# design.net
KiCad netlist of a schematic drawn in EasyEDA
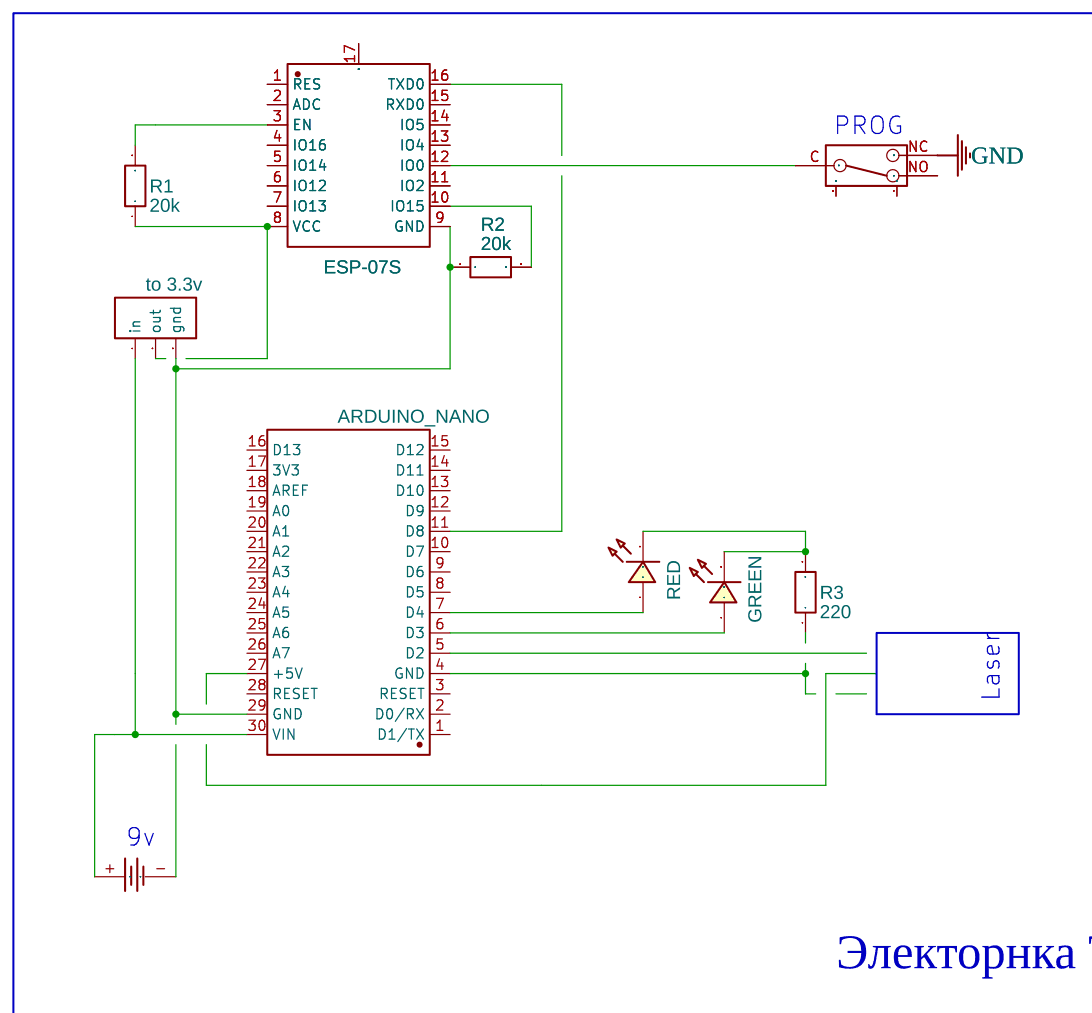
[diagram p0: schematic sheet]

(export (version "E")
  (design (tool "Eeschema 10.0.6"))
  (components
    (comp (ref "B1")
      (value "CR1220-2")
      (fields (field (name "BOM_Supplier Part") "C70381"))
      (libsource (lib "") (part "CR1220-2"))
    )
    (comp (ref "GREEN")
      (value "LED-0603_R")
      (fields
        (field (name "BOM_Manufacturer Part") "19-217/R6C-AL1M2VY/3T")
        (field (name "BOM_Supplier Part") "C72044")
      )
      (libsource (lib "") (part "LED-0603_R_1"))
    )
    (comp (ref "LED1")
      (value "RED")
      (fields
        (field (name "BOM_Manufacturer Part") "19-217/R6C-AL1M2VY/3T")
        (field (name "BOM_Supplier Part") "C72044")
      )
      (libsource (lib "") (part "LED-0603_R"))
    )
    (comp (ref "P1") (value "to 3.3v") (libsource (lib "") (part "CONN-TH_3P-P5.00")))
    (comp (ref "R1") (value "20k") (libsource (lib "") (part "R_0603_EU")))
    (comp (ref "R2") (value "20k") (libsource (lib "") (part "R_0603_EU_1")))
    (comp (ref "R3") (value "220") (libsource (lib "") (part "R_0603_EU")))
    (comp (ref "SW1")
      (value "SK-12D02-VG5")
      (fields (field (name "BOM_Supplier Part") "C136722"))
      (libsource (lib "") (part "SK-12D02-VG5"))
    )
    (comp (ref "U1")
      (value "ARDUINO_NANO")
      (fields (field (name "BOM_Supplier Part") "C9900017879"))
      (libsource (lib "") (part "ARDUINO_NANO"))
    )
    (comp (ref "U2")
      (value "ESP-07S")
      (fields
        (field (name "BOM_Manufacturer Part") "WT8266-S3 ESP-07S")
        (field (name "BOM_Supplier Part") "C477828")
      )
      (libsource (lib "") (part "WT8266-S3 ESP-07S"))
    )
  )
  (nets
    (net (code "1") (name "GND") (class "Default")
      (node (ref "SW1") (pin "NC") (pinfunction "3_NC") (pintype "unspecified"))
    )
    (net (code "2") (name "Net-(B1-1)") (class "Default")
      (node (ref "B1") (pin "+") (pinfunction "1_+") (pintype "input"))
      (node (ref "P1") (pin "1") (pinfunction "in_1") (pintype "unspecified"))
      (node (ref "U1") (pin "30") (pinfunction "VIN_30") (pintype "unspecified"))
    )
    (net (code "3") (name "Net-(GREEN-Pad2)") (class "Default")
      (node (ref "GREEN") (pin "2") (pinfunction "2_2") (pintype "unspecified"))
      (node (ref "LED1") (pin "2") (pinfunction "2_2") (pintype "unspecified"))
      (node (ref "R3") (pin "2") (pinfunction "2_2") (pintype "unspecified"))
    )
    (net (code "4") (name "Net-(P1-gnd)") (class "Default")
      (node (ref "P1") (pin "3") (pinfunction "gnd_3") (pintype "unspecified"))
      (node (ref "R2") (pin "1") (pinfunction "1_1") (pintype "unspecified"))
      (node (ref "U1") (pin "29") (pinfunction "GND_29") (pintype "unspecified"))
      (node (ref "U2") (pin "9") (pinfunction "GND_9") (pintype "unspecified"))
    )
    (net (code "5") (name "Net-(SW1-2)") (class "Default")
      (node (ref "SW1") (pin "C") (pinfunction "2_C") (pintype "unspecified"))
      (node (ref "U2") (pin "12") (pinfunction "IO0_12") (pintype "unspecified"))
    )
    (net (code "6") (name "Net-(U1-D3)") (class "Default")
      (node (ref "GREEN") (pin "1") (pinfunction "1_1") (pintype "unspecified"))
      (node (ref "U1") (pin "6") (pinfunction "D3_6") (pintype "unspecified"))
    )
    (net (code "7") (name "Net-(U1-D4)") (class "Default")
      (node (ref "LED1") (pin "1") (pinfunction "1_1") (pintype "unspecified"))
      (node (ref "U1") (pin "7") (pinfunction "D4_7") (pintype "unspecified"))
    )
    (net (code "8") (name "Net-(U2-EN)") (class "Default")
      (node (ref "R1") (pin "2") (pinfunction "2_2") (pintype "unspecified"))
      (node (ref "U2") (pin "3") (pinfunction "EN_3") (pintype "unspecified"))
    )
    (net (code "9") (name "Net-(U2-IO15)") (class "Default")
      (node (ref "R2") (pin "2") (pinfunction "2_2") (pintype "unspecified"))
      (node (ref "U2") (pin "10") (pinfunction "IO15_10") (pintype "unspecified"))
    )
    (net (code "10") (name "Net-(U2-VCC)") (class "Default")
      (node (ref "R1") (pin "1") (pinfunction "1_1") (pintype "unspecified"))
      (node (ref "U2") (pin "8") (pinfunction "VCC_8") (pintype "unspecified"))
    )
    (net (code "11") (name "unconnected-(B1-2-Pad-)") (class "Default")
      (node (ref "B1") (pin "-") (pinfunction "2_-") (pintype "input"))
    )
    (net (code "12") (name "unconnected-(P1-out-Pad2)") (class "Default")
      (node (ref "P1") (pin "2") (pinfunction "out_2") (pintype "unspecified"))
    )
    (net (code "13") (name "unconnected-(R3-Pad1)") (class "Default")
      (node (ref "R3") (pin "1") (pinfunction "1_1") (pintype "unspecified"))
    )
    (net (code "14") (name "unconnected-(SW1-1-PadNO)") (class "Default")
      (node (ref "SW1") (pin "NO") (pinfunction "1_NO") (pintype "unspecified"))
    )
    (net (code "15") (name "unconnected-(SW1-Pad4)") (class "Default")
      (node (ref "SW1") (pin "4") (pinfunction "4_4") (pintype "unspecified"))
    )
    (net (code "16") (name "unconnected-(SW1-Pad5)") (class "Default")
      (node (ref "SW1") (pin "5") (pinfunction "5_5") (pintype "unspecified"))
    )
    (net (code "17") (name "unconnected-(U1-+5V-Pad27)") (class "Default")
      (node (ref "U1") (pin "27") (pinfunction "+5V_27") (pintype "unspecified"))
    )
    (net (code "18") (name "unconnected-(U1-3V3-Pad17)") (class "Default")
      (node (ref "U1") (pin "17") (pinfunction "3V3_17") (pintype "unspecified"))
    )
    (net (code "19") (name "unconnected-(U1-A0-Pad19)") (class "Default")
      (node (ref "U1") (pin "19") (pinfunction "A0_19") (pintype "unspecified"))
    )
    (net (code "20") (name "unconnected-(U1-A1-Pad20)") (class "Default")
      (node (ref "U1") (pin "20") (pinfunction "A1_20") (pintype "unspecified"))
    )
    (net (code "21") (name "unconnected-(U1-A2-Pad21)") (class "Default")
      (node (ref "U1") (pin "21") (pinfunction "A2_21") (pintype "unspecified"))
    )
    (net (code "22") (name "unconnected-(U1-A3-Pad22)") (class "Default")
      (node (ref "U1") (pin "22") (pinfunction "A3_22") (pintype "unspecified"))
    )
    (net (code "23") (name "unconnected-(U1-A4-Pad23)") (class "Default")
      (node (ref "U1") (pin "23") (pinfunction "A4_23") (pintype "unspecified"))
    )
    (net (code "24") (name "unconnected-(U1-A5-Pad24)") (class "Default")
      (node (ref "U1") (pin "24") (pinfunction "A5_24") (pintype "unspecified"))
    )
    (net (code "25") (name "unconnected-(U1-A6-Pad25)") (class "Default")
      (node (ref "U1") (pin "25") (pinfunction "A6_25") (pintype "unspecified"))
    )
    (net (code "26") (name "unconnected-(U1-A7-Pad26)") (class "Default")
      (node (ref "U1") (pin "26") (pinfunction "A7_26") (pintype "unspecified"))
    )
    (net (code "27") (name "unconnected-(U1-AREF-Pad18)") (class "Default")
      (node (ref "U1") (pin "18") (pinfunction "AREF_18") (pintype "unspecified"))
    )
    (net (code "28") (name "unconnected-(U1-D0{slash}RX-Pad2)") (class "Default")
      (node (ref "U1") (pin "2") (pinfunction "D0/RX_2") (pintype "unspecified"))
    )
    (net (code "29") (name "unconnected-(U1-D1{slash}TX-Pad1)") (class "Default")
      (node (ref "U1") (pin "1") (pinfunction "D1/TX_1") (pintype "unspecified"))
    )
    (net (code "30") (name "unconnected-(U1-D2-Pad5)") (class "Default")
      (node (ref "U1") (pin "5") (pinfunction "D2_5") (pintype "unspecified"))
    )
    (net (code "31") (name "unconnected-(U1-D5-Pad8)") (class "Default")
      (node (ref "U1") (pin "8") (pinfunction "D5_8") (pintype "unspecified"))
    )
    (net (code "32") (name "unconnected-(U1-D6-Pad9)") (class "Default")
      (node (ref "U1") (pin "9") (pinfunction "D6_9") (pintype "unspecified"))
    )
    (net (code "33") (name "unconnected-(U1-D7-Pad10)") (class "Default")
      (node (ref "U1") (pin "10") (pinfunction "D7_10") (pintype "unspecified"))
    )
    (net (code "34") (name "unconnected-(U1-D8-Pad11)") (class "Default")
      (node (ref "U1") (pin "11") (pinfunction "D8_11") (pintype "unspecified"))
    )
    (net (code "35") (name "unconnected-(U1-D9-Pad12)") (class "Default")
      (node (ref "U1") (pin "12") (pinfunction "D9_12") (pintype "unspecified"))
    )
    (net (code "36") (name "unconnected-(U1-D10-Pad13)") (class "Default")
      (node (ref "U1") (pin "13") (pinfunction "D10_13") (pintype "unspecified"))
    )
    (net (code "37") (name "unconnected-(U1-D11-Pad14)") (class "Default")
      (node (ref "U1") (pin "14") (pinfunction "D11_14") (pintype "unspecified"))
    )
    (net (code "38") (name "unconnected-(U1-D12-Pad15)") (class "Default")
      (node (ref "U1") (pin "15") (pinfunction "D12_15") (pintype "unspecified"))
    )
    (net (code "39") (name "unconnected-(U1-D13-Pad16)") (class "Default")
      (node (ref "U1") (pin "16") (pinfunction "D13_16") (pintype "unspecified"))
    )
    (net (code "40") (name "unconnected-(U1-GND-Pad4)") (class "Default")
      (node (ref "U1") (pin "4") (pinfunction "GND_4") (pintype "unspecified"))
    )
    (net (code "41") (name "unconnected-(U1-RESET-Pad3)") (class "Default")
      (node (ref "U1") (pin "3") (pinfunction "RESET_3") (pintype "unspecified"))
    )
    (net (code "42") (name "unconnected-(U1-RESET-Pad28)") (class "Default")
      (node (ref "U1") (pin "28") (pinfunction "RESET_28") (pintype "unspecified"))
    )
    (net (code "43") (name "unconnected-(U2-ADC-Pad2)") (class "Default")
      (node (ref "U2") (pin "2") (pinfunction "ADC_2") (pintype "unspecified"))
    )
    (net (code "44") (name "unconnected-(U2-IO2-Pad11)") (class "Default")
      (node (ref "U2") (pin "11") (pinfunction "IO2_11") (pintype "unspecified"))
    )
    (net (code "45") (name "unconnected-(U2-IO4-Pad13)") (class "Default")
      (node (ref "U2") (pin "13") (pinfunction "IO4_13") (pintype "unspecified"))
    )
    (net (code "46") (name "unconnected-(U2-IO5-Pad14)") (class "Default")
      (node (ref "U2") (pin "14") (pinfunction "IO5_14") (pintype "unspecified"))
    )
    (net (code "47") (name "unconnected-(U2-IO12-Pad6)") (class "Default")
      (node (ref "U2") (pin "6") (pinfunction "IO12_6") (pintype "unspecified"))
    )
    (net (code "48") (name "unconnected-(U2-IO13-Pad7)") (class "Default")
      (node (ref "U2") (pin "7") (pinfunction "IO13_7") (pintype "unspecified"))
    )
    (net (code "49") (name "unconnected-(U2-IO14-Pad5)") (class "Default")
      (node (ref "U2") (pin "5") (pinfunction "IO14_5") (pintype "unspecified"))
    )
    (net (code "50") (name "unconnected-(U2-IO16-Pad4)") (class "Default")
      (node (ref "U2") (pin "4") (pinfunction "IO16_4") (pintype "unspecified"))
    )
    (net (code "51") (name "unconnected-(U2-PAD-Pad17)") (class "Default")
      (node (ref "U2") (pin "17") (pinfunction "PAD_17") (pintype "unspecified"))
    )
    (net (code "52") (name "unconnected-(U2-RES-Pad1)") (class "Default")
      (node (ref "U2") (pin "1") (pinfunction "RES_1") (pintype "unspecified"))
    )
    (net (code "53") (name "unconnected-(U2-RXD0-Pad15)") (class "Default")
      (node (ref "U2") (pin "15") (pinfunction "RXD0_15") (pintype "unspecified"))
    )
    (net (code "54") (name "unconnected-(U2-TXD0-Pad16)") (class "Default")
      (node (ref "U2") (pin "16") (pinfunction "TXD0_16") (pintype "unspecified"))
    )
  )
)
